# MICROCONTROLLER.net
KiCad netlist of a schematic drawn in Altium Designer
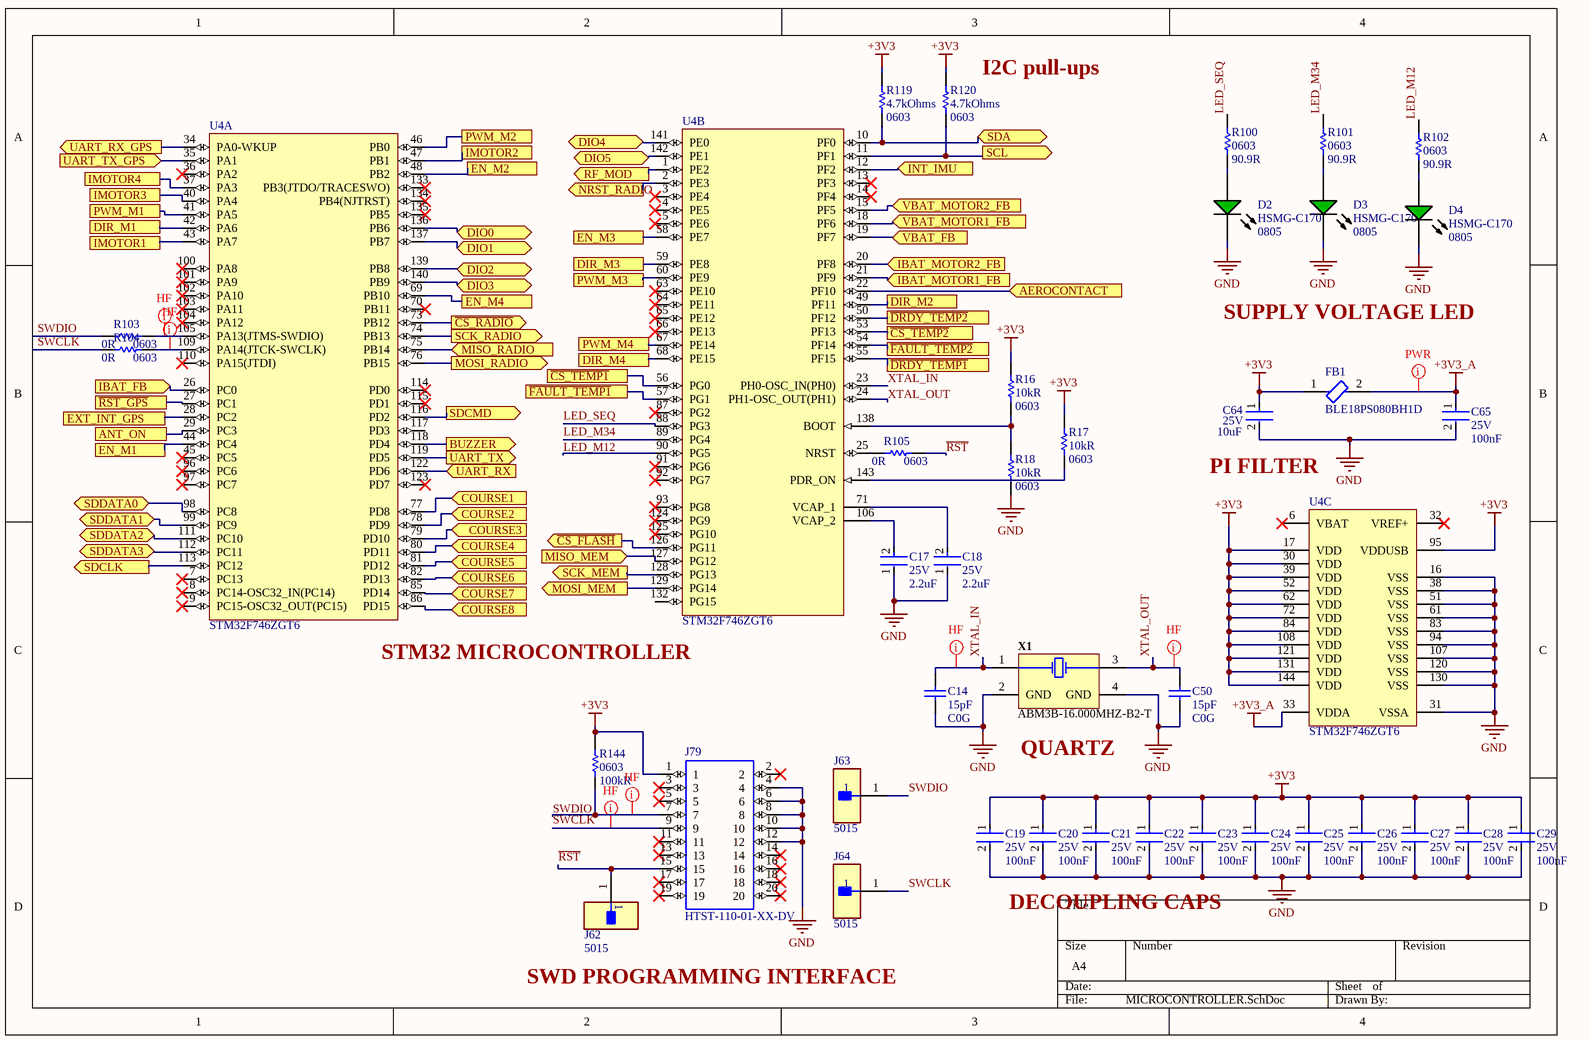
[diagram p0: MICROCONTROLLER.SchDoc]

(export (version "E")
  (design (tool "Eeschema 10.0.6"))
  (components
    (comp (ref "C14")
      (value "VJ0603D150JXPAJ")
      (footprint "CAPC1608X92X38ML15T08")
      (fields
        (field (name "MANUFACTURER") "Vitramon")
        (field (name "TOLERANCE") "5%")
        (field (name "CAPACITANCE") "15pF")
        (field (name "DIELECTRIC") "C0G")
        (field (name "VOLTAGE") "250V")
      )
      (libsource (lib "Altium Content Vault") (part "CAP"))
    )
    (comp (ref "C17")
      (value "C1608X5R1E225K080AB")
      (footprint "FP-C1608-080-0_1-MFG")
      (description "Multilayer Ceramic Capacitors 2.2μF ±10% 25V X5R SMD 0603")
      (fields
        (field (name "VOLTAGE RATING (DC)") "25V")
        (field (name "CAPACITANCE") "2.2uF")
        (field (name "TOLERANCE") "10%")
        (field (name "MANUFACTURER") "TDK")
      )
      (libsource (lib "Altium Content Vault") (part "236180d848d6139a670b325ea6854c9"))
    )
    (comp (ref "C18")
      (value "C1608X5R1E225K080AB")
      (footprint "FP-C1608-080-0_1-MFG")
      (description "Multilayer Ceramic Capacitors 2.2μF ±10% 25V X5R SMD 0603")
      (fields
        (field (name "VOLTAGE RATING (DC)") "25V")
        (field (name "CAPACITANCE") "2.2uF")
        (field (name "TOLERANCE") "10%")
        (field (name "MANUFACTURER") "TDK")
      )
      (libsource (lib "Altium Content Vault") (part "236180d848d6139a670b325ea6854c9"))
    )
    (comp (ref "C19")
      (value "CGA3E2X7R1E104K080AA")
      (footprint "FP-CGA3E-0_3-0_1-MFG")
      (description "Cap Ceramic 100nF 25V X7R 10% Pad SMD 0603 +125°C Automotive T/R")
      (fields
        (field (name "VOLTAGE RATING (DC)") "25V")
        (field (name "CAPACITANCE") "100nF")
        (field (name "TOLERANCE") "10%")
        (field (name "MANUFACTURER") "TDK")
      )
      (libsource (lib "Altium Content Vault") (part "b4654b650e69147ec39a6b967a45e02"))
    )
    (comp (ref "C20")
      (value "CGA3E2X7R1E104K080AA")
      (footprint "FP-CGA3E-0_3-0_1-MFG")
      (description "Cap Ceramic 100nF 25V X7R 10% Pad SMD 0603 +125°C Automotive T/R")
      (fields
        (field (name "VOLTAGE RATING (DC)") "25V")
        (field (name "CAPACITANCE") "100nF")
        (field (name "TOLERANCE") "10%")
        (field (name "MANUFACTURER") "TDK")
      )
      (libsource (lib "Altium Content Vault") (part "b4654b650e69147ec39a6b967a45e02"))
    )
    (comp (ref "C21")
      (value "CGA3E2X7R1E104K080AA")
      (footprint "FP-CGA3E-0_3-0_1-MFG")
      (description "Cap Ceramic 100nF 25V X7R 10% Pad SMD 0603 +125°C Automotive T/R")
      (fields
        (field (name "VOLTAGE RATING (DC)") "25V")
        (field (name "CAPACITANCE") "100nF")
        (field (name "TOLERANCE") "10%")
        (field (name "MANUFACTURER") "TDK")
      )
      (libsource (lib "Altium Content Vault") (part "b4654b650e69147ec39a6b967a45e02"))
    )
    (comp (ref "C22")
      (value "CGA3E2X7R1E104K080AA")
      (footprint "FP-CGA3E-0_3-0_1-MFG")
      (description "Cap Ceramic 100nF 25V X7R 10% Pad SMD 0603 +125°C Automotive T/R")
      (fields
        (field (name "VOLTAGE RATING (DC)") "25V")
        (field (name "CAPACITANCE") "100nF")
        (field (name "TOLERANCE") "10%")
        (field (name "MANUFACTURER") "TDK")
      )
      (libsource (lib "Altium Content Vault") (part "b4654b650e69147ec39a6b967a45e02"))
    )
    (comp (ref "C23")
      (value "CGA3E2X7R1E104K080AA")
      (footprint "FP-CGA3E-0_3-0_1-MFG")
      (description "Cap Ceramic 100nF 25V X7R 10% Pad SMD 0603 +125°C Automotive T/R")
      (fields
        (field (name "VOLTAGE RATING (DC)") "25V")
        (field (name "CAPACITANCE") "100nF")
        (field (name "TOLERANCE") "10%")
        (field (name "MANUFACTURER") "TDK")
      )
      (libsource (lib "Altium Content Vault") (part "b4654b650e69147ec39a6b967a45e02"))
    )
    (comp (ref "C24")
      (value "CGA3E2X7R1E104K080AA")
      (footprint "FP-CGA3E-0_3-0_1-MFG")
      (description "Cap Ceramic 100nF 25V X7R 10% Pad SMD 0603 +125°C Automotive T/R")
      (fields
        (field (name "VOLTAGE RATING (DC)") "25V")
        (field (name "CAPACITANCE") "100nF")
        (field (name "TOLERANCE") "10%")
        (field (name "MANUFACTURER") "TDK")
      )
      (libsource (lib "Altium Content Vault") (part "b4654b650e69147ec39a6b967a45e02"))
    )
    (comp (ref "C25")
      (value "CGA3E2X7R1E104K080AA")
      (footprint "FP-CGA3E-0_3-0_1-MFG")
      (description "Cap Ceramic 100nF 25V X7R 10% Pad SMD 0603 +125°C Automotive T/R")
      (fields
        (field (name "VOLTAGE RATING (DC)") "25V")
        (field (name "CAPACITANCE") "100nF")
        (field (name "TOLERANCE") "10%")
        (field (name "MANUFACTURER") "TDK")
      )
      (libsource (lib "Altium Content Vault") (part "b4654b650e69147ec39a6b967a45e02"))
    )
    (comp (ref "C26")
      (value "CGA3E2X7R1E104K080AA")
      (footprint "FP-CGA3E-0_3-0_1-MFG")
      (description "Cap Ceramic 100nF 25V X7R 10% Pad SMD 0603 +125°C Automotive T/R")
      (fields
        (field (name "VOLTAGE RATING (DC)") "25V")
        (field (name "CAPACITANCE") "100nF")
        (field (name "TOLERANCE") "10%")
        (field (name "MANUFACTURER") "TDK")
      )
      (libsource (lib "Altium Content Vault") (part "b4654b650e69147ec39a6b967a45e02"))
    )
    (comp (ref "C27")
      (value "CGA3E2X7R1E104K080AA")
      (footprint "FP-CGA3E-0_3-0_1-MFG")
      (description "Cap Ceramic 100nF 25V X7R 10% Pad SMD 0603 +125°C Automotive T/R")
      (fields
        (field (name "VOLTAGE RATING (DC)") "25V")
        (field (name "CAPACITANCE") "100nF")
        (field (name "TOLERANCE") "10%")
        (field (name "MANUFACTURER") "TDK")
      )
      (libsource (lib "Altium Content Vault") (part "b4654b650e69147ec39a6b967a45e02"))
    )
    (comp (ref "C28")
      (value "CGA3E2X7R1E104K080AA")
      (footprint "FP-CGA3E-0_3-0_1-MFG")
      (description "Cap Ceramic 100nF 25V X7R 10% Pad SMD 0603 +125°C Automotive T/R")
      (fields
        (field (name "VOLTAGE RATING (DC)") "25V")
        (field (name "CAPACITANCE") "100nF")
        (field (name "TOLERANCE") "10%")
        (field (name "MANUFACTURER") "TDK")
      )
      (libsource (lib "Altium Content Vault") (part "b4654b650e69147ec39a6b967a45e02"))
    )
    (comp (ref "C29")
      (value "CGA3E2X7R1E104K080AA")
      (footprint "FP-CGA3E-0_3-0_1-MFG")
      (description "Cap Ceramic 100nF 25V X7R 10% Pad SMD 0603 +125°C Automotive T/R")
      (fields
        (field (name "VOLTAGE RATING (DC)") "25V")
        (field (name "CAPACITANCE") "100nF")
        (field (name "TOLERANCE") "10%")
        (field (name "MANUFACTURER") "TDK")
      )
      (libsource (lib "Altium Content Vault") (part "b4654b650e69147ec39a6b967a45e02"))
    )
    (comp (ref "C50")
      (value "VJ0603D150JXPAJ")
      (footprint "CAPC1608X92X38ML15T08")
      (fields
        (field (name "MANUFACTURER") "Vitramon")
        (field (name "TOLERANCE") "5%")
        (field (name "CAPACITANCE") "15pF")
        (field (name "DIELECTRIC") "C0G")
        (field (name "VOLTAGE") "250V")
      )
      (libsource (lib "Altium Content Vault") (part "CAP"))
    )
    (comp (ref "C64")
      (value "C2012X5R1E106K125AB")
      (footprint "FP-C2012-125-0_2-IPC_B")
      (description "Multilayer Ceramic Capacitors 10μF ±10% 25V X5R SMD 0805")
      (fields
        (field (name "VOLTAGE") "25V")
        (field (name "VOLTAGE RATING (DC)") "25V")
        (field (name "TOLERANCE") "10%")
        (field (name "CAPACITANCE") "10uF")
      )
      (libsource (lib "Altium Content Vault") (part "b4654b650e69147ec39a6b967a45e02"))
    )
    (comp (ref "C65")
      (value "CGA3E2X7R1E104K080AA")
      (footprint "FP-CGA3E-0_3-0_1-MFG")
      (description "Cap Ceramic 100nF 25V X7R 10% Pad SMD 0603 +125°C Automotive T/R")
      (fields
        (field (name "VOLTAGE RATING (DC)") "25V")
        (field (name "CAPACITANCE") "100nF")
        (field (name "TOLERANCE") "10%")
        (field (name "MANUFACTURER") "TDK")
      )
      (libsource (lib "Altium Content Vault") (part "b4654b650e69147ec39a6b967a45e02"))
    )
    (comp (ref "D2")
      (value "HSMG-C170")
      (footprint "AVAG-HSMX-C170_V")
      (description "Chip LED, Green, 2.2 V, -40 to 85 degC, 2-Pin SMD, Pb-Free, Tape and Reel")
      (fields (field (name "MANUFACTURER") "Avago") (field (name "CASE/PACKAGE") "0805"))
      (libsource (lib "Altium Content Vault") (part "LED_GREEN_A1K2-2"))
    )
    (comp (ref "D3")
      (value "HSMG-C170")
      (footprint "AVAG-HSMX-C170_V")
      (description "Chip LED, Green, 2.2 V, -40 to 85 degC, 2-Pin SMD, Pb-Free, Tape and Reel")
      (fields (field (name "MANUFACTURER") "Avago") (field (name "CASE/PACKAGE") "0805"))
      (libsource (lib "Altium Content Vault") (part "LED_GREEN_A1K2-2"))
    )
    (comp (ref "D4")
      (value "HSMG-C170")
      (footprint "AVAG-HSMX-C170_V")
      (description "Chip LED, Green, 2.2 V, -40 to 85 degC, 2-Pin SMD, Pb-Free, Tape and Reel")
      (fields (field (name "MANUFACTURER") "Avago") (field (name "CASE/PACKAGE") "0805"))
      (libsource (lib "Altium Content Vault") (part "LED_GREEN_A1K2-2"))
    )
    (comp (ref "FB1")
      (value "BLE18PS080BH1D")
      (footprint "FP-BLE18-0_15-t0_6-MFG")
      (description "Ferrite Chip Bead 8.5Ω ±25% 5A, DCR 0.004Ω 0603 AEC-200")
      (fields (field (name "MANUFACTURER") "Murata"))
      (libsource (lib "Altium Content Vault") (part "5f30dd21d616792df468990f7003faa"))
    )
    (comp (ref "J62")
      (value "5015")
      (footprint "FP-5015-MFG")
      (description "PC TEST POINT MINIATURE")
      (fields
        (field (name "MANUFACTURER") "keystone")
        (field (name "OCTOPART") "https://octopart.com/5015-keystone-3822")
      )
      (libsource (lib "Altium Content Vault") (part "dd45045ce8184df9e99e12baf3f412c"))
    )
    (comp (ref "J63")
      (value "5015")
      (footprint "FP-5015-MFG")
      (description "PC TEST POINT MINIATURE")
      (fields
        (field (name "MANUFACTURER") "keystone")
        (field (name "OCTOPART") "https://octopart.com/5015-keystone-3822")
      )
      (libsource (lib "Altium Content Vault") (part "dd45045ce8184df9e99e12baf3f412c"))
    )
    (comp (ref "J64")
      (value "5015")
      (footprint "FP-5015-MFG")
      (description "PC TEST POINT MINIATURE")
      (fields
        (field (name "MANUFACTURER") "keystone")
        (field (name "OCTOPART") "https://octopart.com/5015-keystone-3822")
      )
      (libsource (lib "Altium Content Vault") (part "dd45045ce8184df9e99e12baf3f412c"))
    )
    (comp (ref "J79")
      (value "HTST-110-01-XX-DV")
      (footprint "HTST-110-01-L-DV:HTST-110-01-XX-DV")
      (description "HIGH TEMP TOP SHROUD.")
      (fields (field (name "MF") "{'manufacturer': u'Samtec'}"))
      (libsource (lib "*") (part "HTST-110-01-XX-DV"))
    )
    (comp (ref "R16")
      (value "ERJ3EKF1002V")
      (footprint "RESC1609X55X30LL15T15")
      (description "Chip Resistor, 10 KOhm, +/- 1%, 0.1 W, -55 to 155 degC, 0603 (1608 Metric), RoHS, Tape and Reel")
      (fields
        (field (name "RESISTANCE") "10kR")
        (field (name "CASE CODE (IMPERIAL)") "0603")
        (field (name "TOLERANCE") "1%")
        (field (name "MANUFACTURER") "Panasonic")
      )
      (libsource (lib "Altium Content Vault") (part "RES-2"))
    )
    (comp (ref "R17")
      (value "ERJ3EKF1002V")
      (footprint "RESC1609X55X30LL15T15")
      (description "Chip Resistor, 10 KOhm, +/- 1%, 0.1 W, -55 to 155 degC, 0603 (1608 Metric), RoHS, Tape and Reel")
      (fields
        (field (name "RESISTANCE") "10kR")
        (field (name "CASE CODE (IMPERIAL)") "0603")
        (field (name "TOLERANCE") "1%")
        (field (name "MANUFACTURER") "Panasonic")
      )
      (libsource (lib "Altium Content Vault") (part "RES-2"))
    )
    (comp (ref "R18")
      (value "ERJ3EKF1002V")
      (footprint "RESC1609X55X30LL15T15")
      (description "Chip Resistor, 10 KOhm, +/- 1%, 0.1 W, -55 to 155 degC, 0603 (1608 Metric), RoHS, Tape and Reel")
      (fields
        (field (name "RESISTANCE") "10kR")
        (field (name "CASE CODE (IMPERIAL)") "0603")
        (field (name "TOLERANCE") "1%")
        (field (name "MANUFACTURER") "Panasonic")
      )
      (libsource (lib "Altium Content Vault") (part "RES-2"))
    )
    (comp (ref "R100")
      (value "CRCW060390R9FKEA")
      (footprint "RESC1609X50X30NL10T20")
      (fields
        (field (name "MANUFACTURER") "Vishay Dale")
        (field (name "CASE CODE (IMPERIAL)") "0603")
        (field (name "RESISTANCE") "90.9R")
        (field (name "TOLERANCE") "1%")
      )
      (libsource (lib "Altium Content Vault") (part "RES"))
    )
    (comp (ref "R101")
      (value "CRCW060390R9FKEA")
      (footprint "RESC1609X50X30NL10T20")
      (fields
        (field (name "MANUFACTURER") "Vishay Dale")
        (field (name "CASE CODE (IMPERIAL)") "0603")
        (field (name "RESISTANCE") "90.9R")
        (field (name "TOLERANCE") "1%")
      )
      (libsource (lib "Altium Content Vault") (part "RES"))
    )
    (comp (ref "R102")
      (value "CRCW060390R9FKEA")
      (footprint "RESC1609X50X30NL10T20")
      (fields
        (field (name "MANUFACTURER") "Vishay Dale")
        (field (name "CASE CODE (IMPERIAL)") "0603")
        (field (name "RESISTANCE") "90.9R")
        (field (name "TOLERANCE") "1%")
      )
      (libsource (lib "Altium Content Vault") (part "RES"))
    )
    (comp (ref "R103")
      (value "RC0603JR-070RL")
      (footprint "RESC1608X55X25ML10T15")
      (description "Chip Resistor, 0 Ohm, +/- 5%, 0.1 W, -55 to 155 degC, 0603 (1608 Metric), RoHS, Tape and Reel")
      (fields
        (field (name "TOLERANCE") "5%")
        (field (name "CASE CODE (IMPERIAL)") "0603")
        (field (name "RESISTANCE") "0R")
        (field (name "MANUFACTURER") "Yageo")
      )
      (libsource (lib "Altium Content Vault") (part "RES-2"))
    )
    (comp (ref "R104")
      (value "RC0603JR-070RL")
      (footprint "RESC1608X55X25ML10T15")
      (description "Chip Resistor, 0 Ohm, +/- 5%, 0.1 W, -55 to 155 degC, 0603 (1608 Metric), RoHS, Tape and Reel")
      (fields
        (field (name "TOLERANCE") "5%")
        (field (name "CASE CODE (IMPERIAL)") "0603")
        (field (name "RESISTANCE") "0R")
        (field (name "MANUFACTURER") "Yageo")
      )
      (libsource (lib "Altium Content Vault") (part "RES-2"))
    )
    (comp (ref "R105")
      (value "RC0603JR-070RL")
      (footprint "RESC1608X55X25ML10T15")
      (description "Chip Resistor, 0 Ohm, +/- 5%, 0.1 W, -55 to 155 degC, 0603 (1608 Metric), RoHS, Tape and Reel")
      (fields
        (field (name "TOLERANCE") "5%")
        (field (name "CASE CODE (IMPERIAL)") "0603")
        (field (name "RESISTANCE") "0R")
        (field (name "MANUFACTURER") "Yageo")
      )
      (libsource (lib "Altium Content Vault") (part "RES-2"))
    )
    (comp (ref "R119")
      (value "RC0603FR-074K7L")
      (footprint "RESC1608X55X25LL10T15")
      (description "Chip Resistor, 4.7 KOhm, +/- 1%, 0.1 W, -55 to 155 degC, 0603 (1608 Metric), RoHS, Tape and Reel")
      (fields
        (field (name "MANUFACTURER") "Yageo")
        (field (name "RESISTANCE") "4.7kOhms")
        (field (name "CASE CODE - IN") "0603")
        (field (name "TOLERANCE") "1%")
      )
      (libsource (lib "Altium Content Vault") (part "RES-2"))
    )
    (comp (ref "R120")
      (value "RC0603FR-074K7L")
      (footprint "RESC1608X55X25LL10T15")
      (description "Chip Resistor, 4.7 KOhm, +/- 1%, 0.1 W, -55 to 155 degC, 0603 (1608 Metric), RoHS, Tape and Reel")
      (fields
        (field (name "MANUFACTURER") "Yageo")
        (field (name "RESISTANCE") "4.7kOhms")
        (field (name "CASE CODE - IN") "0603")
        (field (name "TOLERANCE") "1%")
      )
      (libsource (lib "Altium Content Vault") (part "RES-2"))
    )
    (comp (ref "R144")
      (value "ERA3AEB104V")
      (footprint "RESC1608X55X30ML20T20")
      (fields
        (field (name "MANUFACTURER") "Panasonic")
        (field (name "MANUFACTURER PART NUMBER") "ERA-3AEB104V")
        (field (name "CASE CODE (IMPERIAL)") "0603")
        (field (name "RESISTANCE") "100kR")
        (field (name "TOLERANCE") "0.1%")
      )
      (libsource (lib "Altium Content Vault") (part "RES"))
    )
    (comp (ref "U4")
      (value "STM32F746ZGT6")
      (footprint "STM-LQFP144_V")
      (fields (field (name "PARTNUMBER") "STM32F746ZG") (field (name "MANUFACTURER") "STMicroelectronics"))
      (libsource (lib "Altium Content Vault") (part "STM-STM32F74X-LQFP-144"))
    )
    (comp (ref "X1")
      (value "ABM3B-16.000MHZ-B2-T")
      (footprint "ABRA-ABM3B-4_V")
      (description "Ceramic SMD Crystal, 16 MHz, +/- 20 ppm, 50 Ohm, -20 to 70 degC, 4-Pin SMD, RoHS, Tape and Reel")
      (fields (field (name "TOLERANCE") "30%"))
      (libsource (lib "Altium Content Vault") (part "XTAL-1-3-4"))
    )
  )
  (nets
    (net (code "1") (name "+3V3") (class "Default")
      (node (ref "C19") (pin "1") (pinfunction "1_1") (pintype "passive"))
      (node (ref "C20") (pin "1") (pinfunction "1_1") (pintype "passive"))
      (node (ref "C21") (pin "1") (pinfunction "1_1") (pintype "passive"))
      (node (ref "C22") (pin "1") (pinfunction "1_1") (pintype "passive"))
      (node (ref "C23") (pin "1") (pinfunction "1_1") (pintype "passive"))
      (node (ref "C24") (pin "1") (pinfunction "1_1") (pintype "passive"))
      (node (ref "C25") (pin "1") (pinfunction "1_1") (pintype "passive"))
      (node (ref "C26") (pin "1") (pinfunction "1_1") (pintype "passive"))
      (node (ref "C27") (pin "1") (pinfunction "1_1") (pintype "passive"))
      (node (ref "C28") (pin "1") (pinfunction "1_1") (pintype "passive"))
      (node (ref "C29") (pin "1") (pinfunction "1_1") (pintype "passive"))
      (node (ref "C64") (pin "1") (pinfunction "1_1") (pintype "passive"))
      (node (ref "FB1") (pin "1") (pinfunction "1_1") (pintype "passive"))
      (node (ref "J79") (pin "1") (pinfunction "1_1") (pintype "bidirectional"))
      (node (ref "R119") (pin "2") (pinfunction "2_2") (pintype "passive"))
      (node (ref "R120") (pin "2") (pinfunction "2_2") (pintype "passive"))
      (node (ref "R144") (pin "2") (pinfunction "2_2") (pintype "passive"))
      (node (ref "R16") (pin "2") (pinfunction "2_2") (pintype "passive"))
      (node (ref "R17") (pin "2") (pinfunction "2_2") (pintype "passive"))
      (node (ref "U4") (pin "108") (pinfunction "VDD_108") (pintype "power_in"))
      (node (ref "U4") (pin "121") (pinfunction "VDD_121") (pintype "power_in"))
      (node (ref "U4") (pin "131") (pinfunction "VDD_131") (pintype "power_in"))
      (node (ref "U4") (pin "144") (pinfunction "VDD_144") (pintype "power_in"))
      (node (ref "U4") (pin "17") (pinfunction "VDD_17") (pintype "power_in"))
      (node (ref "U4") (pin "30") (pinfunction "VDD_30") (pintype "power_in"))
      (node (ref "U4") (pin "39") (pinfunction "VDD_39") (pintype "power_in"))
      (node (ref "U4") (pin "52") (pinfunction "VDD_52") (pintype "power_in"))
      (node (ref "U4") (pin "62") (pinfunction "VDD_62") (pintype "power_in"))
      (node (ref "U4") (pin "72") (pinfunction "VDD_72") (pintype "power_in"))
      (node (ref "U4") (pin "84") (pinfunction "VDD_84") (pintype "power_in"))
      (node (ref "U4") (pin "95") (pinfunction "VDDUSB_95") (pintype "power_in"))
    )
    (net (code "2") (name "+3V3_A") (class "Default")
      (node (ref "C65") (pin "1") (pinfunction "1_1") (pintype "passive"))
      (node (ref "FB1") (pin "2") (pinfunction "2_2") (pintype "passive"))
      (node (ref "U4") (pin "33") (pinfunction "VDDA_33") (pintype "power_in"))
    )
    (net (code "3") (name "/AEROCONTACT") (class "Default")
      (node (ref "U4") (pin "22") (pinfunction "PF10_22") (pintype "bidirectional"))
    )
    (net (code "4") (name "/ANT_ON") (class "Default")
      (node (ref "U4") (pin "29") (pinfunction "PC3_29") (pintype "bidirectional"))
    )
    (net (code "5") (name "/BUZZER") (class "Default")
      (node (ref "U4") (pin "118") (pinfunction "PD4_118") (pintype "bidirectional"))
    )
    (net (code "6") (name "/COURSE1") (class "Default")
      (node (ref "U4") (pin "77") (pinfunction "PD8_77") (pintype "bidirectional"))
    )
    (net (code "7") (name "/COURSE2") (class "Default")
      (node (ref "U4") (pin "78") (pinfunction "PD9_78") (pintype "bidirectional"))
    )
    (net (code "8") (name "/COURSE3") (class "Default")
      (node (ref "U4") (pin "79") (pinfunction "PD10_79") (pintype "bidirectional"))
    )
    (net (code "9") (name "/COURSE4") (class "Default")
      (node (ref "U4") (pin "80") (pinfunction "PD11_80") (pintype "bidirectional"))
    )
    (net (code "10") (name "/COURSE5") (class "Default")
      (node (ref "U4") (pin "81") (pinfunction "PD12_81") (pintype "bidirectional"))
    )
    (net (code "11") (name "/COURSE6") (class "Default")
      (node (ref "U4") (pin "82") (pinfunction "PD13_82") (pintype "bidirectional"))
    )
    (net (code "12") (name "/COURSE7") (class "Default")
      (node (ref "U4") (pin "85") (pinfunction "PD14_85") (pintype "bidirectional"))
    )
    (net (code "13") (name "/COURSE8") (class "Default")
      (node (ref "U4") (pin "86") (pinfunction "PD15_86") (pintype "bidirectional"))
    )
    (net (code "14") (name "/CS_FLASH") (class "Default")
      (node (ref "U4") (pin "126") (pinfunction "PG11_126") (pintype "bidirectional"))
    )
    (net (code "15") (name "/CS_RADIO") (class "Default")
      (node (ref "U4") (pin "73") (pinfunction "PB12_73") (pintype "bidirectional"))
    )
    (net (code "16") (name "/CS_TEMP1") (class "Default")
      (node (ref "U4") (pin "56") (pinfunction "PG0_56") (pintype "bidirectional"))
    )
    (net (code "17") (name "/CS_TEMP2") (class "Default")
      (node (ref "U4") (pin "53") (pinfunction "PF13_53") (pintype "bidirectional"))
    )
    (net (code "18") (name "/DIO0") (class "Default")
      (node (ref "U4") (pin "136") (pinfunction "PB6_136") (pintype "bidirectional"))
    )
    (net (code "19") (name "/DIO1") (class "Default")
      (node (ref "U4") (pin "137") (pinfunction "PB7_137") (pintype "bidirectional"))
    )
    (net (code "20") (name "/DIO2") (class "Default")
      (node (ref "U4") (pin "139") (pinfunction "PB8_139") (pintype "bidirectional"))
    )
    (net (code "21") (name "/DIO3") (class "Default")
      (node (ref "U4") (pin "140") (pinfunction "PB9_140") (pintype "bidirectional"))
    )
    (net (code "22") (name "/DIO4") (class "Default")
      (node (ref "U4") (pin "141") (pinfunction "PE0_141") (pintype "bidirectional"))
    )
    (net (code "23") (name "/DIO5") (class "Default")
      (node (ref "U4") (pin "142") (pinfunction "PE1_142") (pintype "bidirectional"))
    )
    (net (code "24") (name "/DIR_M1") (class "Default")
      (node (ref "U4") (pin "42") (pinfunction "PA6_42") (pintype "bidirectional"))
    )
    (net (code "25") (name "/DIR_M2") (class "Default")
      (node (ref "U4") (pin "49") (pinfunction "PF11_49") (pintype "bidirectional"))
    )
    (net (code "26") (name "/DIR_M3") (class "Default")
      (node (ref "U4") (pin "59") (pinfunction "PE8_59") (pintype "bidirectional"))
    )
    (net (code "27") (name "/DIR_M4") (class "Default")
      (node (ref "U4") (pin "68") (pinfunction "PE15_68") (pintype "bidirectional"))
    )
    (net (code "28") (name "/DRDY_TEMP1") (class "Default")
      (node (ref "U4") (pin "55") (pinfunction "PF15_55") (pintype "bidirectional"))
    )
    (net (code "29") (name "/DRDY_TEMP2") (class "Default")
      (node (ref "U4") (pin "50") (pinfunction "PF12_50") (pintype "bidirectional"))
    )
    (net (code "30") (name "/EN_M1") (class "Default")
      (node (ref "U4") (pin "44") (pinfunction "PC4_44") (pintype "bidirectional"))
    )
    (net (code "31") (name "/EN_M2") (class "Default")
      (node (ref "U4") (pin "48") (pinfunction "PB2_48") (pintype "bidirectional"))
    )
    (net (code "32") (name "/EN_M3") (class "Default")
      (node (ref "U4") (pin "58") (pinfunction "PE7_58") (pintype "bidirectional"))
    )
    (net (code "33") (name "/EN_M4") (class "Default")
      (node (ref "U4") (pin "69") (pinfunction "PB10_69") (pintype "bidirectional"))
    )
    (net (code "34") (name "/EXT_INT_GPS") (class "Default")
      (node (ref "U4") (pin "28") (pinfunction "PC2_28") (pintype "bidirectional"))
    )
    (net (code "35") (name "/FAULT_TEMP1") (class "Default")
      (node (ref "U4") (pin "57") (pinfunction "PG1_57") (pintype "bidirectional"))
    )
    (net (code "36") (name "/FAULT_TEMP2") (class "Default")
      (node (ref "U4") (pin "54") (pinfunction "PF14_54") (pintype "bidirectional"))
    )
    (net (code "37") (name "/IBAT_FB") (class "Default")
      (node (ref "U4") (pin "26") (pinfunction "PC0_26") (pintype "bidirectional"))
    )
    (net (code "38") (name "/IBAT_MOTOR1_FB") (class "Default")
      (node (ref "U4") (pin "21") (pinfunction "PF9_21") (pintype "bidirectional"))
    )
    (net (code "39") (name "/IBAT_MOTOR2_FB") (class "Default")
      (node (ref "U4") (pin "20") (pinfunction "PF8_20") (pintype "bidirectional"))
    )
    (net (code "40") (name "/IMOTOR1") (class "Default")
      (node (ref "U4") (pin "43") (pinfunction "PA7_43") (pintype "bidirectional"))
    )
    (net (code "41") (name "/IMOTOR2") (class "Default")
      (node (ref "U4") (pin "47") (pinfunction "PB1_47") (pintype "bidirectional"))
    )
    (net (code "42") (name "/IMOTOR3") (class "Default")
      (node (ref "U4") (pin "40") (pinfunction "PA4_40") (pintype "bidirectional"))
    )
    (net (code "43") (name "/IMOTOR4") (class "Default")
      (node (ref "U4") (pin "37") (pinfunction "PA3_37") (pintype "bidirectional"))
    )
    (net (code "44") (name "/INT_IMU") (class "Default")
      (node (ref "U4") (pin "12") (pinfunction "PF2_12") (pintype "bidirectional"))
    )
    (net (code "45") (name "/LED_M12") (class "Default")
      (node (ref "R102") (pin "2") (pinfunction "2_2") (pintype "passive"))
      (node (ref "U4") (pin "90") (pinfunction "PG5_90") (pintype "bidirectional"))
    )
    (net (code "46") (name "/LED_M34") (class "Default")
      (node (ref "R101") (pin "2") (pinfunction "2_2") (pintype "passive"))
      (node (ref "U4") (pin "89") (pinfunction "PG4_89") (pintype "bidirectional"))
    )
    (net (code "47") (name "/LED_SEQ") (class "Default")
      (node (ref "R100") (pin "2") (pinfunction "2_2") (pintype "passive"))
      (node (ref "U4") (pin "88") (pinfunction "PG3_88") (pintype "bidirectional"))
    )
    (net (code "48") (name "/MISO_MEM") (class "Default")
      (node (ref "U4") (pin "127") (pinfunction "PG12_127") (pintype "bidirectional"))
    )
    (net (code "49") (name "/MISO_RADIO") (class "Default")
      (node (ref "U4") (pin "75") (pinfunction "PB14_75") (pintype "bidirectional"))
    )
    (net (code "50") (name "/MOSI_MEM") (class "Default")
      (node (ref "U4") (pin "129") (pinfunction "PG14_129") (pintype "bidirectional"))
    )
    (net (code "51") (name "/MOSI_RADIO") (class "Default")
      (node (ref "U4") (pin "76") (pinfunction "PB15_76") (pintype "bidirectional"))
    )
    (net (code "52") (name "/NRST_RADIO") (class "Default")
      (node (ref "U4") (pin "2") (pinfunction "PE3_2") (pintype "bidirectional"))
    )
    (net (code "53") (name "/PWM_M1") (class "Default")
      (node (ref "U4") (pin "41") (pinfunction "PA5_41") (pintype "bidirectional"))
    )
    (net (code "54") (name "/PWM_M2") (class "Default")
      (node (ref "U4") (pin "46") (pinfunction "PB0_46") (pintype "bidirectional"))
    )
    (net (code "55") (name "/PWM_M3") (class "Default")
      (node (ref "U4") (pin "60") (pinfunction "PE9_60") (pintype "bidirectional"))
    )
    (net (code "56") (name "/PWM_M4") (class "Default")
      (node (ref "U4") (pin "67") (pinfunction "PE14_67") (pintype "bidirectional"))
    )
    (net (code "57") (name "/RF_MOD") (class "Default")
      (node (ref "U4") (pin "1") (pinfunction "PE2_1") (pintype "bidirectional"))
    )
    (net (code "58") (name "/RST") (class "Default")
      (node (ref "J62") (pin "1") (pinfunction "1_1") (pintype "passive"))
      (node (ref "J79") (pin "15") (pinfunction "15_15") (pintype "bidirectional"))
      (node (ref "R105") (pin "2") (pinfunction "2_2") (pintype "passive"))
    )
    (net (code "59") (name "/RST_GPS") (class "Default")
      (node (ref "U4") (pin "27") (pinfunction "PC1_27") (pintype "bidirectional"))
    )
    (net (code "60") (name "/SCK_MEM") (class "Default")
      (node (ref "U4") (pin "128") (pinfunction "PG13_128") (pintype "bidirectional"))
    )
    (net (code "61") (name "/SCK_RADIO") (class "Default")
      (node (ref "U4") (pin "74") (pinfunction "PB13_74") (pintype "bidirectional"))
    )
    (net (code "62") (name "/SCL") (class "Default")
      (node (ref "R120") (pin "1") (pinfunction "1_1") (pintype "passive"))
      (node (ref "U4") (pin "11") (pinfunction "PF1_11") (pintype "bidirectional"))
    )
    (net (code "63") (name "/SDA") (class "Default")
      (node (ref "R119") (pin "1") (pinfunction "1_1") (pintype "passive"))
      (node (ref "U4") (pin "10") (pinfunction "PF0_10") (pintype "bidirectional"))
    )
    (net (code "64") (name "/SDCLK") (class "Default")
      (node (ref "U4") (pin "113") (pinfunction "PC12_113") (pintype "bidirectional"))
    )
    (net (code "65") (name "/SDCMD") (class "Default")
      (node (ref "U4") (pin "116") (pinfunction "PD2_116") (pintype "bidirectional"))
    )
    (net (code "66") (name "/SDDATA0") (class "Default")
      (node (ref "U4") (pin "98") (pinfunction "PC8_98") (pintype "bidirectional"))
    )
    (net (code "67") (name "/SDDATA1") (class "Default")
      (node (ref "U4") (pin "99") (pinfunction "PC9_99") (pintype "bidirectional"))
    )
    (net (code "68") (name "/SDDATA2") (class "Default")
      (node (ref "U4") (pin "111") (pinfunction "PC10_111") (pintype "bidirectional"))
    )
    (net (code "69") (name "/SDDATA3") (class "Default")
      (node (ref "U4") (pin "112") (pinfunction "PC11_112") (pintype "bidirectional"))
    )
    (net (code "70") (name "/SWCLK") (class "Default")
      (node (ref "J64") (pin "1") (pinfunction "1_1") (pintype "passive"))
      (node (ref "J79") (pin "9") (pinfunction "9_9") (pintype "bidirectional"))
      (node (ref "R104") (pin "1") (pinfunction "1_1") (pintype "passive"))
    )
    (net (code "71") (name "/SWDIO") (class "Default")
      (node (ref "J63") (pin "1") (pinfunction "1_1") (pintype "passive"))
      (node (ref "J79") (pin "7") (pinfunction "7_7") (pintype "bidirectional"))
      (node (ref "R103") (pin "1") (pinfunction "1_1") (pintype "passive"))
      (node (ref "R144") (pin "1") (pinfunction "1_1") (pintype "passive"))
    )
    (net (code "72") (name "/UART_RX") (class "Default")
      (node (ref "U4") (pin "122") (pinfunction "PD6_122") (pintype "bidirectional"))
    )
    (net (code "73") (name "/UART_RX_GPS") (class "Default")
      (node (ref "U4") (pin "34") (pinfunction "PA0-WKUP_34") (pintype "bidirectional"))
    )
    (net (code "74") (name "/UART_TX") (class "Default")
      (node (ref "U4") (pin "119") (pinfunction "PD5_119") (pintype "bidirectional"))
    )
    (net (code "75") (name "/UART_TX_GPS") (class "Default")
      (node (ref "U4") (pin "35") (pinfunction "PA1_35") (pintype "bidirectional"))
    )
    (net (code "76") (name "/VBAT_FB") (class "Default")
      (node (ref "U4") (pin "19") (pinfunction "PF7_19") (pintype "bidirectional"))
    )
    (net (code "77") (name "/VBAT_MOTOR1_FB") (class "Default")
      (node (ref "U4") (pin "18") (pinfunction "PF6_18") (pintype "bidirectional"))
    )
    (net (code "78") (name "/VBAT_MOTOR2_FB") (class "Default")
      (node (ref "U4") (pin "15") (pinfunction "PF5_15") (pintype "bidirectional"))
    )
    (net (code "79") (name "/XTAL_IN") (class "Default")
      (node (ref "C14") (pin "2") (pinfunction "2_2") (pintype "passive"))
      (node (ref "U4") (pin "23") (pinfunction "PH0-OSC_IN(PH0)_23") (pintype "bidirectional"))
      (node (ref "X1") (pin "1") (pinfunction "X1_1") (pintype "passive"))
    )
    (net (code "80") (name "/XTAL_OUT") (class "Default")
      (node (ref "C50") (pin "2") (pinfunction "2_2") (pintype "passive"))
      (node (ref "U4") (pin "24") (pinfunction "PH1-OSC_OUT(PH1)_24") (pintype "bidirectional"))
      (node (ref "X1") (pin "3") (pinfunction "X2_3") (pintype "passive"))
    )
    (net (code "81") (name "GND") (class "Default")
      (node (ref "C14") (pin "1") (pinfunction "1_1") (pintype "passive"))
      (node (ref "C17") (pin "1") (pinfunction "1_1") (pintype "passive"))
      (node (ref "C18") (pin "1") (pinfunction "1_1") (pintype "passive"))
      (node (ref "C19") (pin "2") (pinfunction "2_2") (pintype "passive"))
      (node (ref "C20") (pin "2") (pinfunction "2_2") (pintype "passive"))
      (node (ref "C21") (pin "2") (pinfunction "2_2") (pintype "passive"))
      (node (ref "C22") (pin "2") (pinfunction "2_2") (pintype "passive"))
      (node (ref "C23") (pin "2") (pinfunction "2_2") (pintype "passive"))
      (node (ref "C24") (pin "2") (pinfunction "2_2") (pintype "passive"))
      (node (ref "C25") (pin "2") (pinfunction "2_2") (pintype "passive"))
      (node (ref "C26") (pin "2") (pinfunction "2_2") (pintype "passive"))
      (node (ref "C27") (pin "2") (pinfunction "2_2") (pintype "passive"))
      (node (ref "C28") (pin "2") (pinfunction "2_2") (pintype "passive"))
      (node (ref "C29") (pin "2") (pinfunction "2_2") (pintype "passive"))
      (node (ref "C50") (pin "1") (pinfunction "1_1") (pintype "passive"))
      (node (ref "C64") (pin "2") (pinfunction "2_2") (pintype "passive"))
      (node (ref "C65") (pin "2") (pinfunction "2_2") (pintype "passive"))
      (node (ref "D2") (pin "2") (pinfunction "K_2") (pintype "passive"))
      (node (ref "D3") (pin "2") (pinfunction "K_2") (pintype "passive"))
      (node (ref "D4") (pin "2") (pinfunction "K_2") (pintype "passive"))
      (node (ref "J79") (pin "10") (pinfunction "10_10") (pintype "bidirectional"))
      (node (ref "J79") (pin "12") (pinfunction "12_12") (pintype "bidirectional"))
      (node (ref "J79") (pin "4") (pinfunction "4_4") (pintype "bidirectional"))
      (node (ref "J79") (pin "6") (pinfunction "6_6") (pintype "bidirectional"))
      (node (ref "J79") (pin "8") (pinfunction "8_8") (pintype "bidirectional"))
      (node (ref "R18") (pin "1") (pinfunction "1_1") (pintype "passive"))
      (node (ref "U4") (pin "107") (pinfunction "VSS_107") (pintype "power_in"))
      (node (ref "U4") (pin "120") (pinfunction "VSS_120") (pintype "power_in"))
      (node (ref "U4") (pin "130") (pinfunction "VSS_130") (pintype "power_in"))
      (node (ref "U4") (pin "16") (pinfunction "VSS_16") (pintype "power_in"))
      (node (ref "U4") (pin "31") (pinfunction "VSSA_31") (pintype "power_in"))
      (node (ref "U4") (pin "38") (pinfunction "VSS_38") (pintype "power_in"))
      (node (ref "U4") (pin "51") (pinfunction "VSS_51") (pintype "power_in"))
      (node (ref "U4") (pin "61") (pinfunction "VSS_61") (pintype "power_in"))
      (node (ref "U4") (pin "83") (pinfunction "VSS_83") (pintype "power_in"))
      (node (ref "U4") (pin "94") (pinfunction "VSS_94") (pintype "power_in"))
      (node (ref "X1") (pin "2") (pinfunction "GND_2") (pintype "power_in"))
      (node (ref "X1") (pin "4") (pinfunction "GND_4") (pintype "power_in"))
    )
    (net (code "82") (name "Net-(D2-A)") (class "Default")
      (node (ref "D2") (pin "1") (pinfunction "A_1") (pintype "passive"))
      (node (ref "R100") (pin "1") (pinfunction "1_1") (pintype "passive"))
    )
    (net (code "83") (name "Net-(D3-A)") (class "Default")
      (node (ref "D3") (pin "1") (pinfunction "A_1") (pintype "passive"))
      (node (ref "R101") (pin "1") (pinfunction "1_1") (pintype "passive"))
    )
    (net (code "84") (name "Net-(D4-A)") (class "Default")
      (node (ref "D4") (pin "1") (pinfunction "A_1") (pintype "passive"))
      (node (ref "R102") (pin "1") (pinfunction "1_1") (pintype "passive"))
    )
    (net (code "85") (name "Net-(U4A-PA13(JTMS-SWDIO))") (class "Default")
      (node (ref "R103") (pin "2") (pinfunction "2_2") (pintype "passive"))
      (node (ref "U4") (pin "105") (pinfunction "PA13(JTMS-SWDIO)_105") (pintype "bidirectional"))
    )
    (net (code "86") (name "Net-(U4A-PA14(JTCK-SWCLK))") (class "Default")
      (node (ref "R104") (pin "2") (pinfunction "2_2") (pintype "passive"))
      (node (ref "U4") (pin "109") (pinfunction "PA14(JTCK-SWCLK)_109") (pintype "bidirectional"))
    )
    (net (code "87") (name "Net-(U4B-BOOT)") (class "Default")
      (node (ref "R16") (pin "1") (pinfunction "1_1") (pintype "passive"))
      (node (ref "R18") (pin "2") (pinfunction "2_2") (pintype "passive"))
      (node (ref "U4") (pin "138") (pinfunction "BOOT_138") (pintype "input"))
    )
    (net (code "88") (name "Net-(U4B-NRST)") (class "Default")
      (node (ref "R105") (pin "1") (pinfunction "1_1") (pintype "passive"))
      (node (ref "U4") (pin "25") (pinfunction "NRST_25") (pintype "bidirectional"))
    )
    (net (code "89") (name "Net-(U4B-PDR_ON)") (class "Default")
      (node (ref "R17") (pin "1") (pinfunction "1_1") (pintype "passive"))
      (node (ref "U4") (pin "143") (pinfunction "PDR_ON_143") (pintype "input"))
    )
    (net (code "90") (name "Net-(U4B-VCAP_1)") (class "Default")
      (node (ref "C18") (pin "2") (pinfunction "2_2") (pintype "passive"))
      (node (ref "U4") (pin "71") (pinfunction "VCAP_1_71") (pintype "power_in"))
    )
    (net (code "91") (name "Net-(U4B-VCAP_2)") (class "Default")
      (node (ref "C17") (pin "2") (pinfunction "2_2") (pintype "passive"))
      (node (ref "U4") (pin "106") (pinfunction "VCAP_2_106") (pintype "power_in"))
    )
    (net (code "92") (name "unconnected-(J79-Pad2)") (class "Default")
      (node (ref "J79") (pin "2") (pinfunction "2_2") (pintype "bidirectional+no_connect"))
    )
    (net (code "93") (name "unconnected-(J79-Pad3)") (class "Default")
      (node (ref "J79") (pin "3") (pinfunction "3_3") (pintype "bidirectional+no_connect"))
    )
    (net (code "94") (name "unconnected-(J79-Pad5)") (class "Default")
      (node (ref "J79") (pin "5") (pinfunction "5_5") (pintype "bidirectional+no_connect"))
    )
    (net (code "95") (name "unconnected-(J79-Pad11)") (class "Default")
      (node (ref "J79") (pin "11") (pinfunction "11_11") (pintype "bidirectional+no_connect"))
    )
    (net (code "96") (name "unconnected-(J79-Pad13)") (class "Default")
      (node (ref "J79") (pin "13") (pinfunction "13_13") (pintype "bidirectional+no_connect"))
    )
    (net (code "97") (name "unconnected-(J79-Pad14)") (class "Default")
      (node (ref "J79") (pin "14") (pinfunction "14_14") (pintype "bidirectional+no_connect"))
    )
    (net (code "98") (name "unconnected-(J79-Pad16)") (class "Default")
      (node (ref "J79") (pin "16") (pinfunction "16_16") (pintype "bidirectional+no_connect"))
    )
    (net (code "99") (name "unconnected-(J79-Pad17)") (class "Default")
      (node (ref "J79") (pin "17") (pinfunction "17_17") (pintype "bidirectional+no_connect"))
    )
    (net (code "100") (name "unconnected-(J79-Pad18)") (class "Default")
      (node (ref "J79") (pin "18") (pinfunction "18_18") (pintype "bidirectional+no_connect"))
    )
    (net (code "101") (name "unconnected-(J79-Pad19)") (class "Default")
      (node (ref "J79") (pin "19") (pinfunction "19_19") (pintype "bidirectional+no_connect"))
    )
    (net (code "102") (name "unconnected-(J79-Pad20)") (class "Default")
      (node (ref "J79") (pin "20") (pinfunction "20_20") (pintype "bidirectional+no_connect"))
    )
    (net (code "103") (name "unconnected-(U4A-PA2-Pad36)") (class "Default")
      (node (ref "U4") (pin "36") (pinfunction "PA2_36") (pintype "bidirectional+no_connect"))
    )
    (net (code "104") (name "unconnected-(U4A-PA8-Pad100)") (class "Default")
      (node (ref "U4") (pin "100") (pinfunction "PA8_100") (pintype "bidirectional+no_connect"))
    )
    (net (code "105") (name "unconnected-(U4A-PA9-Pad101)") (class "Default")
      (node (ref "U4") (pin "101") (pinfunction "PA9_101") (pintype "bidirectional+no_connect"))
    )
    (net (code "106") (name "unconnected-(U4A-PA10-Pad102)") (class "Default")
      (node (ref "U4") (pin "102") (pinfunction "PA10_102") (pintype "bidirectional+no_connect"))
    )
    (net (code "107") (name "unconnected-(U4A-PA11-Pad103)") (class "Default")
      (node (ref "U4") (pin "103") (pinfunction "PA11_103") (pintype "bidirectional+no_connect"))
    )
    (net (code "108") (name "unconnected-(U4A-PA12-Pad104)") (class "Default")
      (node (ref "U4") (pin "104") (pinfunction "PA12_104") (pintype "bidirectional+no_connect"))
    )
    (net (code "109") (name "unconnected-(U4A-PA15(JTDI)-Pad110)") (class "Default")
      (node (ref "U4") (pin "110") (pinfunction "PA15(JTDI)_110") (pintype "bidirectional+no_connect"))
    )
    (net (code "110") (name "unconnected-(U4A-PB3(JTDO{slash}TRACESWO)-Pad133)") (class "Default")
      (node (ref "U4") (pin "133") (pinfunction "PB3(JTDO/TRACESWO)_133") (pintype "bidirectional+no_connect"))
    )
    (net (code "111") (name "unconnected-(U4A-PB4(NJTRST)-Pad134)") (class "Default")
      (node (ref "U4") (pin "134") (pinfunction "PB4(NJTRST)_134") (pintype "bidirectional+no_connect"))
    )
    (net (code "112") (name "unconnected-(U4A-PB5-Pad135)") (class "Default")
      (node (ref "U4") (pin "135") (pinfunction "PB5_135") (pintype "bidirectional+no_connect"))
    )
    (net (code "113") (name "unconnected-(U4A-PB11-Pad70)") (class "Default")
      (node (ref "U4") (pin "70") (pinfunction "PB11_70") (pintype "bidirectional+no_connect"))
    )
    (net (code "114") (name "unconnected-(U4A-PC5-Pad45)") (class "Default")
      (node (ref "U4") (pin "45") (pinfunction "PC5_45") (pintype "bidirectional+no_connect"))
    )
    (net (code "115") (name "unconnected-(U4A-PC6-Pad96)") (class "Default")
      (node (ref "U4") (pin "96") (pinfunction "PC6_96") (pintype "bidirectional+no_connect"))
    )
    (net (code "116") (name "unconnected-(U4A-PC7-Pad97)") (class "Default")
      (node (ref "U4") (pin "97") (pinfunction "PC7_97") (pintype "bidirectional+no_connect"))
    )
    (net (code "117") (name "unconnected-(U4A-PC13-Pad7)") (class "Default")
      (node (ref "U4") (pin "7") (pinfunction "PC13_7") (pintype "bidirectional+no_connect"))
    )
    (net (code "118") (name "unconnected-(U4A-PC14-OSC32_IN(PC14)-Pad8)") (class "Default")
      (node (ref "U4") (pin "8") (pinfunction "PC14-OSC32_IN(PC14)_8") (pintype "bidirectional+no_connect"))
    )
    (net (code "119") (name "unconnected-(U4A-PC15-OSC32_OUT(PC15)-Pad9)") (class "Default")
      (node (ref "U4") (pin "9") (pinfunction "PC15-OSC32_OUT(PC15)_9") (pintype "bidirectional+no_connect"))
    )
    (net (code "120") (name "unconnected-(U4A-PD0-Pad114)") (class "Default")
      (node (ref "U4") (pin "114") (pinfunction "PD0_114") (pintype "bidirectional+no_connect"))
    )
    (net (code "121") (name "unconnected-(U4A-PD1-Pad115)") (class "Default")
      (node (ref "U4") (pin "115") (pinfunction "PD1_115") (pintype "bidirectional+no_connect"))
    )
    (net (code "122") (name "unconnected-(U4A-PD3-Pad117)") (class "Default")
      (node (ref "U4") (pin "117") (pinfunction "PD3_117") (pintype "bidirectional"))
    )
    (net (code "123") (name "unconnected-(U4A-PD7-Pad123)") (class "Default")
      (node (ref "U4") (pin "123") (pinfunction "PD7_123") (pintype "bidirectional+no_connect"))
    )
    (net (code "124") (name "unconnected-(U4B-PE4-Pad3)") (class "Default")
      (node (ref "U4") (pin "3") (pinfunction "PE4_3") (pintype "bidirectional+no_connect"))
    )
    (net (code "125") (name "unconnected-(U4B-PE5-Pad4)") (class "Default")
      (node (ref "U4") (pin "4") (pinfunction "PE5_4") (pintype "bidirectional+no_connect"))
    )
    (net (code "126") (name "unconnected-(U4B-PE6-Pad5)") (class "Default")
      (node (ref "U4") (pin "5") (pinfunction "PE6_5") (pintype "bidirectional+no_connect"))
    )
    (net (code "127") (name "unconnected-(U4B-PE10-Pad63)") (class "Default")
      (node (ref "U4") (pin "63") (pinfunction "PE10_63") (pintype "bidirectional+no_connect"))
    )
    (net (code "128") (name "unconnected-(U4B-PE11-Pad64)") (class "Default")
      (node (ref "U4") (pin "64") (pinfunction "PE11_64") (pintype "bidirectional+no_connect"))
    )
    (net (code "129") (name "unconnected-(U4B-PE12-Pad65)") (class "Default")
      (node (ref "U4") (pin "65") (pinfunction "PE12_65") (pintype "bidirectional+no_connect"))
    )
    (net (code "130") (name "unconnected-(U4B-PE13-Pad66)") (class "Default")
      (node (ref "U4") (pin "66") (pinfunction "PE13_66") (pintype "bidirectional+no_connect"))
    )
    (net (code "131") (name "unconnected-(U4B-PF3-Pad13)") (class "Default")
      (node (ref "U4") (pin "13") (pinfunction "PF3_13") (pintype "bidirectional+no_connect"))
    )
    (net (code "132") (name "unconnected-(U4B-PF4-Pad14)") (class "Default")
      (node (ref "U4") (pin "14") (pinfunction "PF4_14") (pintype "bidirectional+no_connect"))
    )
    (net (code "133") (name "unconnected-(U4B-PG2-Pad87)") (class "Default")
      (node (ref "U4") (pin "87") (pinfunction "PG2_87") (pintype "bidirectional+no_connect"))
    )
    (net (code "134") (name "unconnected-(U4B-PG6-Pad91)") (class "Default")
      (node (ref "U4") (pin "91") (pinfunction "PG6_91") (pintype "bidirectional+no_connect"))
    )
    (net (code "135") (name "unconnected-(U4B-PG7-Pad92)") (class "Default")
      (node (ref "U4") (pin "92") (pinfunction "PG7_92") (pintype "bidirectional+no_connect"))
    )
    (net (code "136") (name "unconnected-(U4B-PG8-Pad93)") (class "Default")
      (node (ref "U4") (pin "93") (pinfunction "PG8_93") (pintype "bidirectional+no_connect"))
    )
    (net (code "137") (name "unconnected-(U4B-PG9-Pad124)") (class "Default")
      (node (ref "U4") (pin "124") (pinfunction "PG9_124") (pintype "bidirectional+no_connect"))
    )
    (net (code "138") (name "unconnected-(U4B-PG10-Pad125)") (class "Default")
      (node (ref "U4") (pin "125") (pinfunction "PG10_125") (pintype "bidirectional+no_connect"))
    )
    (net (code "139") (name "unconnected-(U4B-PG15-Pad132)") (class "Default")
      (node (ref "U4") (pin "132") (pinfunction "PG15_132") (pintype "bidirectional"))
    )
    (net (code "140") (name "unconnected-(U4C-VBAT-Pad6)") (class "Default")
      (node (ref "U4") (pin "6") (pinfunction "VBAT_6") (pintype "power_in+no_connect"))
    )
    (net (code "141") (name "unconnected-(U4C-VREF+-Pad32)") (class "Default")
      (node (ref "U4") (pin "32") (pinfunction "VREF+_32") (pintype "power_in+no_connect"))
    )
  )
)
